# SerialPort.net
KiCad netlist of a schematic drawn in Altium Designer
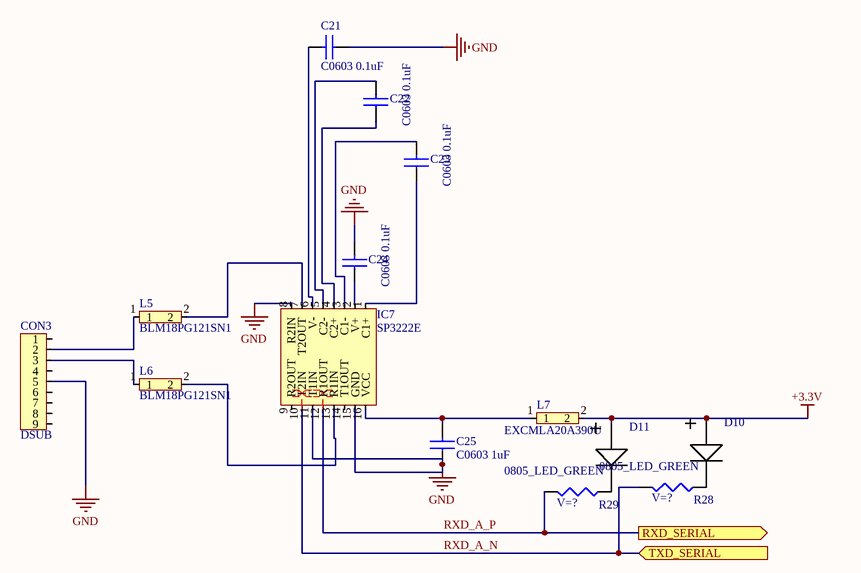
[diagram p0: SerialPort.SchDoc]

(export (version "E")
  (design (tool "Eeschema 10.0.6"))
  (components
    (comp (ref "C21")
      (value "C0603 0.1uF")
      (footprint "C0603")
      (description "CAP CER 0.1uF 16V X7R 0603 / CL10B104K08NNNC")
      (libsource (lib "COOP4403_BerkantAY") (part "C0603 0.1uF"))
    )
    (comp (ref "C22")
      (value "C0603 0.1uF")
      (footprint "C0603")
      (description "CAP CER 0.1uF 16V X7R 0603 / CL10B104K08NNNC")
      (libsource (lib "COOP4403_BerkantAY") (part "C0603 0.1uF"))
    )
    (comp (ref "C23")
      (value "C0603 0.1uF")
      (footprint "C0603")
      (description "CAP CER 0.1uF 16V X7R 0603 / CL10B104K08NNNC")
      (libsource (lib "COOP4403_BerkantAY") (part "C0603 0.1uF"))
    )
    (comp (ref "C24")
      (value "C0603 0.1uF")
      (footprint "C0603")
      (description "CAP CER 0.1uF 16V X7R 0603 / CL10B104K08NNNC")
      (libsource (lib "COOP4403_BerkantAY") (part "C0603 0.1uF"))
    )
    (comp (ref "C25")
      (value "C0603 1uF")
      (footprint "C0603")
      (description "CAP CER 1uF 10V X7R 0603")
      (libsource (lib "COOP4403_BerkantAY") (part "C0603 1uF"))
    )
    (comp (ref "CON3")
      (value "DSUB")
      (footprint "DSUB")
      (description "1734354 - DSUB")
      (libsource (lib "COOP4403_BerkantAY") (part "DSUB"))
    )
    (comp (ref "D10")
      (value "0805_LED_GREEN")
      (footprint "0805LED_GREEN")
      (description "LGR971-KN OSRAM")
      (libsource (lib "COOP4403_BerkantAY") (part "0805_LED_GREEN"))
    )
    (comp (ref "D11")
      (value "0805_LED_GREEN")
      (footprint "0805LED_GREEN")
      (description "LGR971-KN OSRAM")
      (libsource (lib "COOP4403_BerkantAY") (part "0805_LED_GREEN"))
    )
    (comp (ref "IC7")
      (value "SP3222E")
      (footprint "SSOP16")
      (description "IC TXRX RS232 ESD TRUE 16SSOP")
      (libsource (lib "COOP4403_BerkantAY") (part "SP3222E"))
    )
    (comp (ref "L5")
      (value "BLM18PG121SN1")
      (footprint "C0603")
      (description "FERRITE BEAD 120OHM 2A")
      (libsource (lib "COOP4403_BerkantAY") (part "BLM18PG121SN1"))
    )
    (comp (ref "L6")
      (value "BLM18PG121SN1")
      (footprint "C0603")
      (description "FERRITE BEAD 120OHM 2A")
      (libsource (lib "COOP4403_BerkantAY") (part "BLM18PG121SN1"))
    )
    (comp (ref "L7")
      (value "EXCMLA20A390U")
      (footprint "L0805")
      (description "FERRITE BEAD 39 OHM")
      (libsource (lib "COOP4403_BerkantAY") (part "EXCMLA20A390U"))
    )
    (comp (ref "R28")
      (value "V=?")
      (footprint "r0402")
      (description "RESISTOR")
      (libsource (lib "COOP4403_BerkantAY") (part "R0402"))
    )
    (comp (ref "R29")
      (value "V=?")
      (footprint "r0402")
      (description "RESISTOR")
      (libsource (lib "COOP4403_BerkantAY") (part "R0402"))
    )
  )
  (nets
    (net (code "1") (name "+3.3V") (class "Default")
      (node (ref "D10") (pin "2") (pinfunction "2_2") (pintype "passive"))
      (node (ref "D11") (pin "2") (pinfunction "2_2") (pintype "passive"))
      (node (ref "L7") (pin "2") (pinfunction "2_2") (pintype "passive"))
    )
    (net (code "2") (name "/RXD_A_N") (class "Default")
      (node (ref "IC7") (pin "10") (pinfunction "T2IN_10") (pintype "passive"))
      (node (ref "R28") (pin "2") (pinfunction "2_2") (pintype "passive"))
    )
    (net (code "3") (name "/RXD_A_P") (class "Default")
      (node (ref "IC7") (pin "12") (pinfunction "R1OUT_12") (pintype "passive"))
      (node (ref "R29") (pin "2") (pinfunction "2_2") (pintype "passive"))
    )
    (net (code "4") (name "GND") (class "Default")
      (node (ref "C21") (pin "1") (pinfunction "1_1") (pintype "passive"))
      (node (ref "C24") (pin "2") (pinfunction "2_2") (pintype "passive"))
      (node (ref "C25") (pin "1") (pinfunction "1_1") (pintype "passive"))
      (node (ref "CON3") (pin "5") (pinfunction "5_5") (pintype "passive"))
      (node (ref "IC7") (pin "11") (pinfunction "T1IN_11") (pintype "passive"))
      (node (ref "IC7") (pin "15") (pinfunction "GND_15") (pintype "passive"))
      (node (ref "IC7") (pin "8") (pinfunction "R2IN_8") (pintype "passive"))
    )
    (net (code "5") (name "Net-(CON3-Pad2)") (class "Default")
      (node (ref "CON3") (pin "2") (pinfunction "2_2") (pintype "passive"))
      (node (ref "L5") (pin "1") (pinfunction "1_1") (pintype "passive"))
    )
    (net (code "6") (name "Net-(CON3-Pad3)") (class "Default")
      (node (ref "CON3") (pin "3") (pinfunction "3_3") (pintype "passive"))
      (node (ref "L6") (pin "1") (pinfunction "1_1") (pintype "passive"))
    )
    (net (code "7") (name "Net-(D10-Pad1)") (class "Default")
      (node (ref "D10") (pin "1") (pinfunction "1_1") (pintype "passive"))
      (node (ref "R28") (pin "1") (pinfunction "1_1") (pintype "passive"))
    )
    (net (code "8") (name "Net-(D11-Pad1)") (class "Default")
      (node (ref "D11") (pin "1") (pinfunction "1_1") (pintype "passive"))
      (node (ref "R29") (pin "1") (pinfunction "1_1") (pintype "passive"))
    )
    (net (code "9") (name "Net-(IC7-C1+)") (class "Default")
      (node (ref "C23") (pin "1") (pinfunction "1_1") (pintype "passive"))
      (node (ref "IC7") (pin "1") (pinfunction "C1+_1") (pintype "passive"))
    )
    (net (code "10") (name "Net-(IC7-C1-)") (class "Default")
      (node (ref "C23") (pin "2") (pinfunction "2_2") (pintype "passive"))
      (node (ref "IC7") (pin "3") (pinfunction "C1-_3") (pintype "passive"))
    )
    (net (code "11") (name "Net-(IC7-C2+)") (class "Default")
      (node (ref "C22") (pin "1") (pinfunction "1_1") (pintype "passive"))
      (node (ref "IC7") (pin "4") (pinfunction "C2+_4") (pintype "passive"))
    )
    (net (code "12") (name "Net-(IC7-C2-)") (class "Default")
      (node (ref "C22") (pin "2") (pinfunction "2_2") (pintype "passive"))
      (node (ref "IC7") (pin "5") (pinfunction "C2-_5") (pintype "passive"))
    )
    (net (code "13") (name "Net-(IC7-R1IN)") (class "Default")
      (node (ref "IC7") (pin "13") (pinfunction "R1IN_13") (pintype "passive"))
      (node (ref "L6") (pin "2") (pinfunction "2_2") (pintype "passive"))
    )
    (net (code "14") (name "Net-(IC7-T2OUT)") (class "Default")
      (node (ref "IC7") (pin "7") (pinfunction "T2OUT_7") (pintype "passive"))
      (node (ref "L5") (pin "2") (pinfunction "2_2") (pintype "passive"))
    )
    (net (code "15") (name "Net-(IC7-V+)") (class "Default")
      (node (ref "C24") (pin "1") (pinfunction "1_1") (pintype "passive"))
      (node (ref "IC7") (pin "2") (pinfunction "V+_2") (pintype "passive"))
    )
    (net (code "16") (name "Net-(IC7-V-)") (class "Default")
      (node (ref "C21") (pin "2") (pinfunction "2_2") (pintype "passive"))
      (node (ref "IC7") (pin "6") (pinfunction "V-_6") (pintype "passive"))
    )
    (net (code "17") (name "Net-(IC7-VCC)") (class "Default")
      (node (ref "C25") (pin "2") (pinfunction "2_2") (pintype "passive"))
      (node (ref "IC7") (pin "16") (pinfunction "VCC_16") (pintype "passive"))
      (node (ref "L7") (pin "1") (pinfunction "1_1") (pintype "passive"))
    )
    (net (code "18") (name "unconnected-(CON3-Pad1)") (class "Default")
      (node (ref "CON3") (pin "1") (pinfunction "1_1") (pintype "passive"))
    )
    (net (code "19") (name "unconnected-(CON3-Pad4)") (class "Default")
      (node (ref "CON3") (pin "4") (pinfunction "4_4") (pintype "passive"))
    )
    (net (code "20") (name "unconnected-(CON3-Pad6)") (class "Default")
      (node (ref "CON3") (pin "6") (pinfunction "6_6") (pintype "passive"))
    )
    (net (code "21") (name "unconnected-(CON3-Pad7)") (class "Default")
      (node (ref "CON3") (pin "7") (pinfunction "7_7") (pintype "passive"))
    )
    (net (code "22") (name "unconnected-(CON3-Pad8)") (class "Default")
      (node (ref "CON3") (pin "8") (pinfunction "8_8") (pintype "passive"))
    )
    (net (code "23") (name "unconnected-(CON3-Pad9)") (class "Default")
      (node (ref "CON3") (pin "9") (pinfunction "9_9") (pintype "passive"))
    )
    (net (code "24") (name "unconnected-(IC7-R2OUT-Pad9)") (class "Default")
      (node (ref "IC7") (pin "9") (pinfunction "R2OUT_9") (pintype "passive"))
    )
    (net (code "25") (name "unconnected-(IC7-T1OUT-Pad14)") (class "Default")
      (node (ref "IC7") (pin "14") (pinfunction "T1OUT_14") (pintype "passive"))
    )
  )
)
